# SCH__HMI.net
KiCad netlist of a schematic drawn in Altium Designer
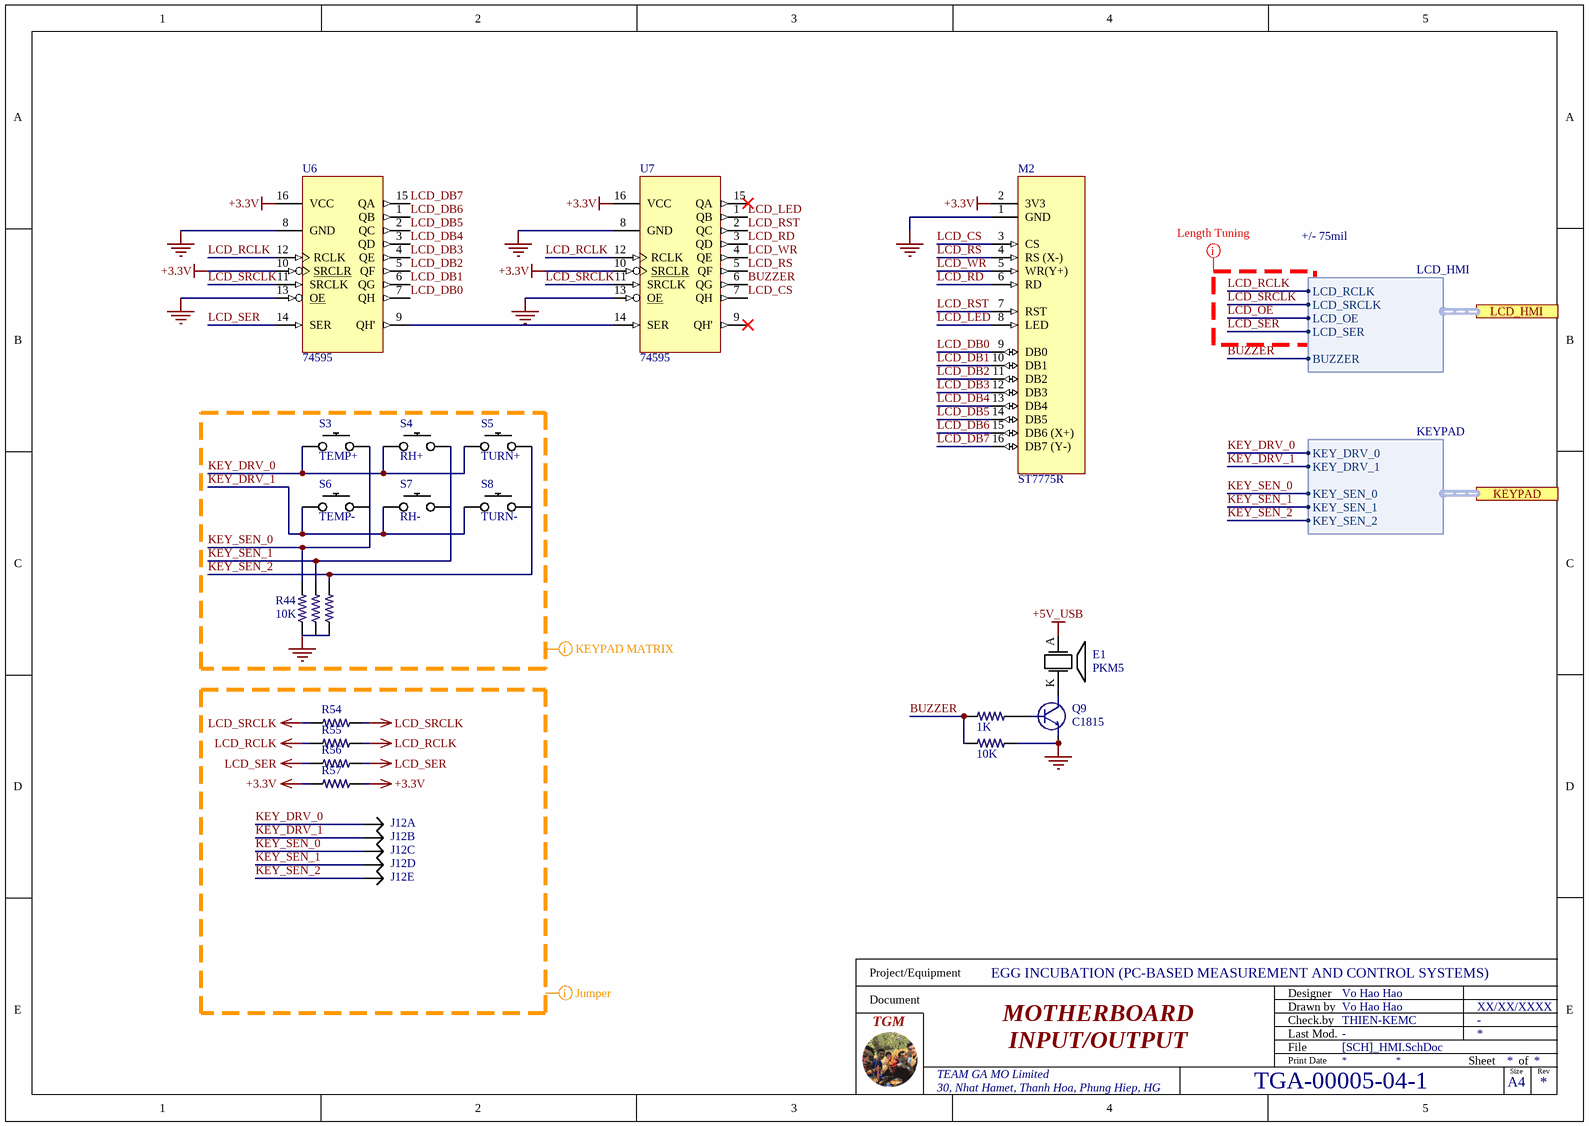
[diagram p0: [SCH]_HMI.SchDoc]

(export (version "E")
  (design (tool "Eeschema 10.0.6"))
  (components
    (comp (ref "E1")
      (value "PKM5")
      (footprint "BUZZER")
      (description "ALARM-AUDIBLE PIEZO ALARM PIN TYPE; 5V")
      (libsource (lib "TOAN_VERSION_1_0") (part "BUZZER"))
    )
    (comp (ref "J12")
      (value "KEYPAD")
      (footprint "Header 5P")
      (libsource (lib "TOAN_VERSION_1_0") (part "JP5"))
    )
    (comp (ref "M2")
      (value "ST7775R")
      (footprint "LCD_176X220_MODULE")
      (libsource (lib "TOAN_VERSION_1_0") (part "LCD_176x220"))
    )
    (comp (ref "Q9")
      (value "C1815")
      (footprint "SOT23(123)")
      (description "Transistor, NPN, RF, 50mA, 12V")
      (libsource (lib "TOAN_VERSION_1_0") (part "NPN"))
    )
    (comp (ref "R44")
      (value "10K")
      (footprint "RES-SMD-0805")
      (description "Chip Resistor, 0805, 1%, 1/8 W")
      (fields (field (name "Comment") "RES-2512-4.7R"))
      (libsource (lib "TOAN_VERSION_1_0") (part "RES"))
    )
    (comp (ref "R45")
      (value "RES-2512-4.7R")
      (footprint "RES-SMD-0805")
      (description "Chip Resistor, 0805, 1%, 1/8 W")
      (libsource (lib "TOAN_VERSION_1_0") (part "RES"))
    )
    (comp (ref "R46")
      (value "RES-2512-4.7R")
      (footprint "RES-SMD-0805")
      (description "Chip Resistor, 0805, 1%, 1/8 W")
      (libsource (lib "TOAN_VERSION_1_0") (part "RES"))
    )
    (comp (ref "R47")
      (value "1K")
      (footprint "RES-SMD-0805")
      (description "Chip Resistor, 0805, 1%, 1/8 W")
      (fields (field (name "Comment") "RES-2512-4.7R"))
      (libsource (lib "TOAN_VERSION_1_0") (part "RES"))
    )
    (comp (ref "R48")
      (value "10K")
      (footprint "RES-SMD-0805")
      (description "Chip Resistor, 0805, 1%, 1/8 W")
      (fields (field (name "Comment") "RES-2512-4.7R"))
      (libsource (lib "TOAN_VERSION_1_0") (part "RES"))
    )
    (comp (ref "R54")
      (value "R0805")
      (footprint "RES-SMD-0805")
      (description "Chip Resistor, 0805, 1%, 1/8 W")
      (libsource (lib "TOAN_VERSION_1_0") (part "RES"))
    )
    (comp (ref "R55")
      (value "R0805")
      (footprint "RES-SMD-0805")
      (description "Chip Resistor, 0805, 1%, 1/8 W")
      (libsource (lib "TOAN_VERSION_1_0") (part "RES"))
    )
    (comp (ref "R56")
      (value "R0805")
      (footprint "RES-SMD-0805")
      (description "Chip Resistor, 0805, 1%, 1/8 W")
      (libsource (lib "TOAN_VERSION_1_0") (part "RES"))
    )
    (comp (ref "R57")
      (value "R0805")
      (footprint "RES-SMD-0805")
      (description "Chip Resistor, 0805, 1%, 1/8 W")
      (libsource (lib "TOAN_VERSION_1_0") (part "RES"))
    )
    (comp (ref "S3")
      (value "TEMP+")
      (footprint "Header 2P")
      (description "SWITCH TACTILE SPST-NO 0.05A 12V")
      (fields (field (name "MANUFACTURER PART NUMBER") "TL3342F260QG"))
      (libsource (lib "TOAN_VERSION_1_0") (part "SWITCH TACTILE SPST"))
    )
    (comp (ref "S4")
      (value "RH+")
      (footprint "Header 2P")
      (description "SWITCH TACTILE SPST-NO 0.05A 12V")
      (fields (field (name "MANUFACTURER PART NUMBER") "TL3342F260QG"))
      (libsource (lib "TOAN_VERSION_1_0") (part "SWITCH TACTILE SPST"))
    )
    (comp (ref "S5")
      (value "TURN+")
      (footprint "Header 2P")
      (description "SWITCH TACTILE SPST-NO 0.05A 12V")
      (fields (field (name "MANUFACTURER PART NUMBER") "TL3342F260QG"))
      (libsource (lib "TOAN_VERSION_1_0") (part "SWITCH TACTILE SPST"))
    )
    (comp (ref "S6")
      (value "TEMP-")
      (footprint "Header 2P")
      (description "SWITCH TACTILE SPST-NO 0.05A 12V")
      (fields (field (name "MANUFACTURER PART NUMBER") "TL3342F260QG"))
      (libsource (lib "TOAN_VERSION_1_0") (part "SWITCH TACTILE SPST"))
    )
    (comp (ref "S7")
      (value "RH-")
      (footprint "Header 2P")
      (description "SWITCH TACTILE SPST-NO 0.05A 12V")
      (fields (field (name "MANUFACTURER PART NUMBER") "TL3342F260QG"))
      (libsource (lib "TOAN_VERSION_1_0") (part "SWITCH TACTILE SPST"))
    )
    (comp (ref "S8")
      (value "TURN-")
      (footprint "Header 2P")
      (description "SWITCH TACTILE SPST-NO 0.05A 12V")
      (fields (field (name "MANUFACTURER PART NUMBER") "TL3342F260QG"))
      (libsource (lib "TOAN_VERSION_1_0") (part "SWITCH TACTILE SPST"))
    )
    (comp (ref "U6")
      (value "74595")
      (footprint "SOIC-16S")
      (description "CD74HC595 8-Bit Shift Registers With 3-State Output Registers")
      (libsource (lib "TOAN_VERSION_1_0") (part "74595"))
    )
    (comp (ref "U7")
      (value "74595")
      (footprint "SOIC-16S")
      (description "CD74HC595 8-Bit Shift Registers With 3-State Output Registers")
      (libsource (lib "TOAN_VERSION_1_0") (part "74595"))
    )
  )
  (nets
    (net (code "3") (name "+3.3V") (class "Default")
      (node (ref "M2") (pin "2") (pinfunction "3V3_2") (pintype "power_in"))
      (node (ref "R57") (pin "1") (pintype "passive"))
      (node (ref "R57") (pin "2") (pintype "passive"))
      (node (ref "U6") (pin "10") (pinfunction "SRCLR_10") (pintype "input"))
      (node (ref "U6") (pin "16") (pinfunction "VCC_16") (pintype "power_in"))
      (node (ref "U7") (pin "10") (pinfunction "SRCLR_10") (pintype "input"))
      (node (ref "U7") (pin "16") (pinfunction "VCC_16") (pintype "power_in"))
    )
    (net (code "4") (name "+5V_USB") (class "Default")
      (node (ref "E1") (pin "A") (pinfunction "A_A") (pintype "passive"))
    )
    (net (code "5") (name "/BUZZER") (class "Default")
      (node (ref "R47") (pin "1") (pintype "passive"))
      (node (ref "R48") (pin "1") (pintype "passive"))
      (node (ref "U7") (pin "6") (pinfunction "QG_6") (pintype "output"))
    )
    (net (code "6") (name "/KEY_DRV_0") (class "Default")
      (node (ref "J12") (pin "1") (pinfunction "1_1") (pintype "passive"))
      (node (ref "S3") (pin "1") (pinfunction "1_1") (pintype "passive"))
      (node (ref "S4") (pin "1") (pinfunction "1_1") (pintype "passive"))
      (node (ref "S5") (pin "1") (pinfunction "1_1") (pintype "passive"))
    )
    (net (code "7") (name "/KEY_DRV_1") (class "Default")
      (node (ref "J12") (pin "2") (pinfunction "2_2") (pintype "passive"))
      (node (ref "S6") (pin "1") (pinfunction "1_1") (pintype "passive"))
      (node (ref "S7") (pin "1") (pinfunction "1_1") (pintype "passive"))
      (node (ref "S8") (pin "1") (pinfunction "1_1") (pintype "passive"))
    )
    (net (code "8") (name "/KEY_SEN_0") (class "Default")
      (node (ref "J12") (pin "3") (pinfunction "3_3") (pintype "passive"))
      (node (ref "R44") (pin "1") (pintype "passive"))
      (node (ref "S3") (pin "1") (pinfunction "1_1") (pintype "passive"))
      (node (ref "S6") (pin "1") (pinfunction "1_1") (pintype "passive"))
    )
    (net (code "9") (name "/KEY_SEN_1") (class "Default")
      (node (ref "J12") (pin "4") (pinfunction "4_4") (pintype "passive"))
      (node (ref "R45") (pin "1") (pintype "passive"))
      (node (ref "S4") (pin "1") (pinfunction "1_1") (pintype "passive"))
      (node (ref "S7") (pin "1") (pinfunction "1_1") (pintype "passive"))
    )
    (net (code "10") (name "/KEY_SEN_2") (class "Default")
      (node (ref "J12") (pin "5") (pinfunction "5_5") (pintype "passive"))
      (node (ref "R46") (pin "1") (pintype "passive"))
      (node (ref "S5") (pin "1") (pinfunction "1_1") (pintype "passive"))
      (node (ref "S8") (pin "1") (pinfunction "1_1") (pintype "passive"))
    )
    (net (code "11") (name "/LCD_CS") (class "Default")
      (node (ref "M2") (pin "3") (pinfunction "CS_3") (pintype "input"))
      (node (ref "U7") (pin "7") (pinfunction "QH_7") (pintype "output"))
    )
    (net (code "12") (name "/LCD_DB0") (class "Default")
      (node (ref "M2") (pin "9") (pinfunction "DB0_9") (pintype "bidirectional"))
      (node (ref "U6") (pin "7") (pinfunction "QH_7") (pintype "output"))
    )
    (net (code "13") (name "/LCD_DB1") (class "Default")
      (node (ref "M2") (pin "10") (pinfunction "DB1_10") (pintype "bidirectional"))
      (node (ref "U6") (pin "6") (pinfunction "QG_6") (pintype "output"))
    )
    (net (code "14") (name "/LCD_DB2") (class "Default")
      (node (ref "M2") (pin "11") (pinfunction "DB2_11") (pintype "bidirectional"))
      (node (ref "U6") (pin "5") (pinfunction "QF_5") (pintype "output"))
    )
    (net (code "15") (name "/LCD_DB3") (class "Default")
      (node (ref "M2") (pin "12") (pinfunction "DB3_12") (pintype "bidirectional"))
      (node (ref "U6") (pin "4") (pinfunction "QE_4") (pintype "output"))
    )
    (net (code "16") (name "/LCD_DB4") (class "Default")
      (node (ref "M2") (pin "13") (pinfunction "DB4_13") (pintype "bidirectional"))
      (node (ref "U6") (pin "3") (pinfunction "QD_3") (pintype "output"))
    )
    (net (code "17") (name "/LCD_DB5") (class "Default")
      (node (ref "M2") (pin "14") (pinfunction "DB5_14") (pintype "bidirectional"))
      (node (ref "U6") (pin "2") (pinfunction "QC_2") (pintype "output"))
    )
    (net (code "18") (name "/LCD_DB6") (class "Default")
      (node (ref "M2") (pin "15") (pinfunction "DB6_(X+)_15") (pintype "bidirectional"))
      (node (ref "U6") (pin "1") (pinfunction "QB_1") (pintype "output"))
    )
    (net (code "19") (name "/LCD_DB7") (class "Default")
      (node (ref "M2") (pin "16") (pinfunction "DB7_(Y-)_16") (pintype "bidirectional"))
      (node (ref "U6") (pin "15") (pinfunction "QA_15") (pintype "output"))
    )
    (net (code "20") (name "/LCD_LED") (class "Default")
      (node (ref "M2") (pin "8") (pinfunction "LED_8") (pintype "input"))
      (node (ref "U7") (pin "1") (pinfunction "QB_1") (pintype "output"))
    )
    (net (code "22") (name "/LCD_RD") (class "Default")
      (node (ref "M2") (pin "6") (pinfunction "RD_6") (pintype "input"))
      (node (ref "U7") (pin "3") (pinfunction "QD_3") (pintype "output"))
    )
    (net (code "23") (name "/LCD_RS") (class "Default")
      (node (ref "M2") (pin "4") (pinfunction "RS_(X-)_4") (pintype "input"))
      (node (ref "U7") (pin "5") (pinfunction "QF_5") (pintype "output"))
    )
    (net (code "24") (name "/LCD_RST") (class "Default")
      (node (ref "M2") (pin "7") (pinfunction "RST_7") (pintype "input"))
      (node (ref "U7") (pin "2") (pinfunction "QC_2") (pintype "output"))
    )
    (net (code "25") (name "/LCD_WR") (class "Default")
      (node (ref "M2") (pin "5") (pinfunction "WR(Y+)_5") (pintype "input"))
      (node (ref "U7") (pin "4") (pinfunction "QE_4") (pintype "output"))
    )
    (net (code "28") (name "GND") (class "Default")
      (node (ref "M2") (pin "1") (pinfunction "GND_1") (pintype "power_in"))
      (node (ref "Q9") (pin "3") (pinfunction "E_3") (pintype "passive"))
      (node (ref "R44") (pin "2") (pintype "passive"))
      (node (ref "R45") (pin "2") (pintype "passive"))
      (node (ref "R46") (pin "2") (pintype "passive"))
      (node (ref "R48") (pin "2") (pintype "passive"))
      (node (ref "U6") (pin "13") (pinfunction "OE_13") (pintype "input"))
      (node (ref "U6") (pin "8") (pinfunction "GND_8") (pintype "power_in"))
      (node (ref "U7") (pin "13") (pinfunction "OE_13") (pintype "input"))
      (node (ref "U7") (pin "8") (pinfunction "GND_8") (pintype "power_in"))
    )
    (net (code "29") (name "LCD_RCLK") (class "Default")
      (node (ref "R55") (pin "1") (pintype "passive"))
      (node (ref "R55") (pin "2") (pintype "passive"))
      (node (ref "U6") (pin "12") (pinfunction "RCLK_12") (pintype "input"))
      (node (ref "U7") (pin "12") (pinfunction "RCLK_12") (pintype "input"))
    )
    (net (code "30") (name "LCD_SER") (class "Default")
      (node (ref "R56") (pin "1") (pintype "passive"))
      (node (ref "R56") (pin "2") (pintype "passive"))
      (node (ref "U6") (pin "14") (pinfunction "SER_14") (pintype "input"))
    )
    (net (code "31") (name "LCD_SRCLK") (class "Default")
      (node (ref "R54") (pin "1") (pintype "passive"))
      (node (ref "R54") (pin "2") (pintype "passive"))
      (node (ref "U6") (pin "11") (pinfunction "SRCLK_11") (pintype "input"))
      (node (ref "U7") (pin "11") (pinfunction "SRCLK_11") (pintype "input"))
    )
    (net (code "32") (name "Net-(Q9-B)") (class "Default")
      (node (ref "Q9") (pin "1") (pinfunction "B_1") (pintype "passive"))
      (node (ref "R47") (pin "2") (pintype "passive"))
    )
    (net (code "33") (name "Net-(Q9-C)") (class "Default")
      (node (ref "E1") (pin "K") (pinfunction "K_K") (pintype "passive"))
      (node (ref "Q9") (pin "2") (pinfunction "C_2") (pintype "passive"))
    )
    (net (code "34") (name "Net-(U6-QH')") (class "Default")
      (node (ref "U6") (pin "9") (pinfunction "QH'_9") (pintype "output"))
      (node (ref "U7") (pin "14") (pinfunction "SER_14") (pintype "input"))
    )
    (net (code "35") (name "unconnected-(U7-QA-Pad15)") (class "Default")
      (node (ref "U7") (pin "15") (pinfunction "QA_15") (pintype "output+no_connect"))
    )
    (net (code "36") (name "unconnected-(U7-QH'-Pad9)") (class "Default")
      (node (ref "U7") (pin "9") (pinfunction "QH'_9") (pintype "output+no_connect"))
    )
  )
)
